# PL2303_HX.net
KiCad netlist of a schematic drawn in Altium Designer
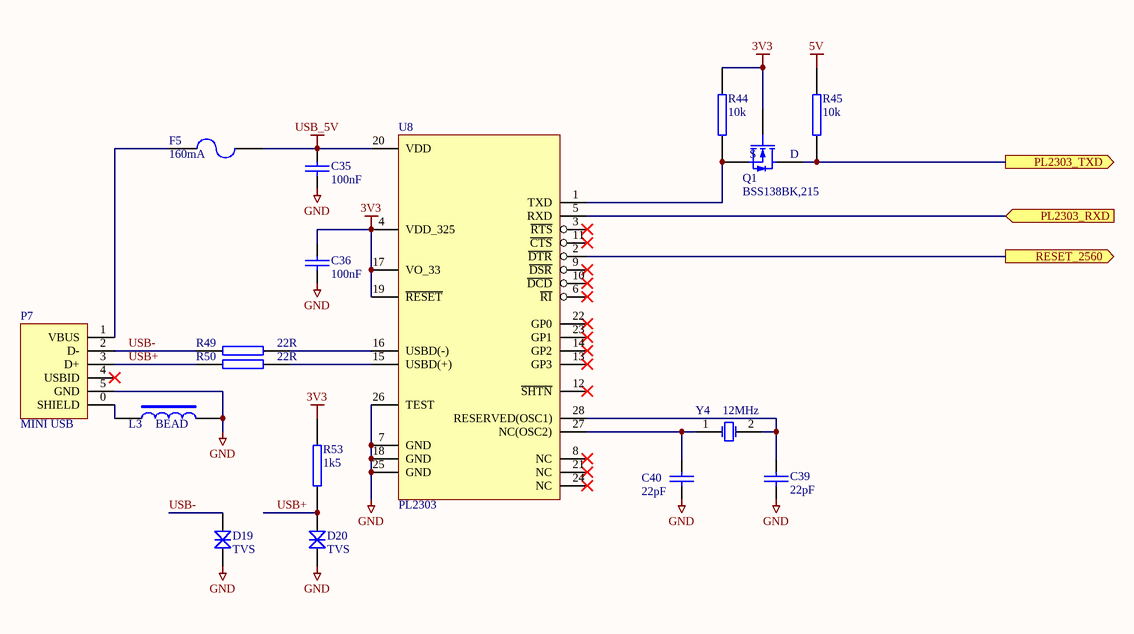
[diagram p0: PL2303(HX).SchDoc]

(export (version "E")
  (design (tool "Eeschema 10.0.6"))
  (components
    (comp (ref "C35")
      (value "100nF")
      (footprint "CAP (3D) - 0603")
      (description "CAPACITOR SMD 0603")
      (fields (field (name "MOUSER PART NO.") "81-GCM188R71C104KA7D") (field (name "MANUFACTURER") "Murata"))
      (libsource (lib "NASCO Capacitors") (part "CAP SMD 0603 100nF"))
    )
    (comp (ref "C36")
      (value "100nF")
      (footprint "CAP (3D) - 0603")
      (description "CAPACITOR SMD 0603")
      (fields (field (name "MOUSER PART NO.") "81-GCM188R71C104KA7D") (field (name "MANUFACTURER") "Murata"))
      (libsource (lib "NASCO Capacitors") (part "CAP SMD 0603 100nF"))
    )
    (comp (ref "C39")
      (value "22pF")
      (footprint "CAP (3D) - 0603")
      (description "CAPACITOR SMD 0603")
      (fields
        (field (name "MANUFACTURER") "Vishay")
        (field (name "MANUFACTURER PART NO.") "VJ0603A220JXACW1BC")
      )
      (libsource (lib "NASCO Capacitors") (part "CAP SMD 0603 1nF"))
    )
    (comp (ref "C40")
      (value "22pF")
      (footprint "CAP (3D) - 0603")
      (description "CAPACITOR SMD 0603")
      (fields
        (field (name "MANUFACTURER") "Vishay")
        (field (name "MANUFACTURER PART NO.") "VJ0603A220JXACW1BC")
      )
      (libsource (lib "NASCO Capacitors") (part "CAP SMD 0603 1nF"))
    )
    (comp (ref "D19")
      (value "TVS")
      (footprint "TVS (3D) - 0603")
      (description "Transient Voltage Suppression (TVS) Diode")
      (fields (field (name "MANUFACTURER PART NO.") "CG0603MLC-05E") (field (name "MANUFACTURER") "Bourns"))
      (libsource (lib "SIM900") (part "TVS DIODE"))
    )
    (comp (ref "D20")
      (value "TVS")
      (footprint "TVS (3D) - 0603")
      (description "Transient Voltage Suppression (TVS) Diode")
      (fields (field (name "MANUFACTURER PART NO.") "CG0603MLC-05E") (field (name "MANUFACTURER") "Bourns"))
      (libsource (lib "SIM900") (part "TVS DIODE"))
    )
    (comp (ref "F5")
      (value "160mA")
      (footprint "1206")
      (description "Fuse")
      (fields (field (name "MANUFACTURER") "Littlefuse") (field (name "MOUSER PART NO.") "576-1206L016WR"))
      (libsource (lib "Miscellaneous Devices") (part "Fuse 2"))
    )
    (comp (ref "L3")
      (value "BEAD")
      (footprint "RES (3D) - 1210")
      (description "INDUCTOR SMD 1210")
      (fields (field (name "MOUSER PART NO.") "636-2512063007Y3") (field (name "MANUFACTURER") "Fair-Rite"))
      (libsource (lib "NASCO") (part "INDUCTOR SMD 1210 100uH"))
    )
    (comp (ref "P7")
      (value "MINI USB")
      (footprint "MINI USB")
      (description "MICRO USB")
      (fields
        (field (name "MANUFACTURER") "Keystone Electronics")
        (field (name "MANUFACTURER PART NO.") "534-934")
      )
      (libsource (lib "SIM900") (part "MICRO USB"))
    )
    (comp (ref "Q1")
      (value "BSS138BK,215")
      (footprint "SOT23-3L")
      (description "N-Channel MOSFET")
      (fields
        (field (name "MANUFACTURER") "NXP Semiconductors")
        (field (name "MOUSER PART NO.") "771-BSS138BK215")
      )
      (libsource (lib "SIM900") (part "BSS138BK,215 SOT23"))
    )
    (comp (ref "R44")
      (value "10k")
      (footprint "RES (3D) - 0603")
      (description "RESISTOR SMD 0603 10k")
      (fields (field (name "MOUSER PART NO.") "652-CR0603FX-1002ELF") (field (name "MANUFACTURER") "Bourns"))
      (libsource (lib "NASCO Resistors") (part "RES SMD 0603 10k"))
    )
    (comp (ref "R45")
      (value "10k")
      (footprint "RES (3D) - 0603")
      (description "RESISTOR SMD 0603 10k")
      (fields (field (name "MOUSER PART NO.") "652-CR0603FX-1002ELF") (field (name "MANUFACTURER") "Bourns"))
      (libsource (lib "NASCO Resistors") (part "RES SMD 0603 10k"))
    )
    (comp (ref "R49")
      (value "22R")
      (footprint "RES (3D) - 0603")
      (description "RESISTOR SMD 0603 0R")
      (fields (field (name "MANUFACTURER") "Xicon") (field (name "MANUFACTURER PART NO.") "301-22-RC"))
      (libsource (lib "NASCO Resistors") (part "RES SMD 0603 0R"))
    )
    (comp (ref "R50")
      (value "22R")
      (footprint "RES (3D) - 0603")
      (description "RESISTOR SMD 0603 0R")
      (fields (field (name "MANUFACTURER") "Xicon") (field (name "MANUFACTURER PART NO.") "301-22-RC"))
      (libsource (lib "NASCO Resistors") (part "RES SMD 0603 0R"))
    )
    (comp (ref "R53")
      (value "1k5")
      (footprint "RES (3D) - 0603")
      (description "RESISTOR SMD 0603 0R")
      (libsource (lib "NASCO Resistors") (part "RES SMD 0603 0R"))
    )
    (comp (ref "U8")
      (value "PL2303")
      (footprint "SSOP28")
      (description "PL2303 USB to 232 Converter (FT232 Compatible)")
      (fields (field (name "MANUFACTURER") "PROLIFIC") (field (name "MANUFACTURER PART NO.") "PL2303TA"))
      (libsource (lib "NASCO") (part "PL2303"))
    )
    (comp (ref "Y4")
      (value "12MHz")
      (footprint "HC49/4H_SMX")
      (description "Crystal Oscillator")
      (fields (field (name "MANUFACTURER") "ECS"))
      (libsource (lib "Miscellaneous Devices") (part "XTAL"))
    )
  )
  (nets
    (net (code "1") (name "/PL2303_RXD") (class "Default")
      (node (ref "U8") (pin "5") (pinfunction "RXD_5") (pintype "passive"))
    )
    (net (code "2") (name "/PL2303_TXD") (class "Default")
      (node (ref "Q1") (pin "3") (pinfunction "D_3") (pintype "passive"))
      (node (ref "R45") (pin "1") (pinfunction "1_1") (pintype "passive"))
    )
    (net (code "3") (name "/RESET_2560") (class "Default")
      (node (ref "U8") (pin "2") (pinfunction "~{DTR}_2") (pintype "passive"))
    )
    (net (code "4") (name "/USB+") (class "Default")
      (node (ref "D20") (pin "2") (pinfunction "K_2") (pintype "passive"))
      (node (ref "P7") (pin "3") (pinfunction "D+_3") (pintype "passive"))
      (node (ref "R50") (pin "1") (pinfunction "1_1") (pintype "passive"))
      (node (ref "R53") (pin "2") (pinfunction "2_2") (pintype "passive"))
    )
    (net (code "5") (name "/USB-") (class "Default")
      (node (ref "D19") (pin "2") (pinfunction "K_2") (pintype "passive"))
      (node (ref "P7") (pin "2") (pinfunction "D-_2") (pintype "passive"))
      (node (ref "R49") (pin "1") (pinfunction "1_1") (pintype "passive"))
    )
    (net (code "6") (name "3V3") (class "Default")
      (node (ref "C36") (pin "1") (pinfunction "1_1") (pintype "passive"))
      (node (ref "Q1") (pin "1") (pinfunction "G_1") (pintype "passive"))
      (node (ref "R44") (pin "2") (pinfunction "2_2") (pintype "passive"))
      (node (ref "R53") (pin "1") (pinfunction "1_1") (pintype "passive"))
      (node (ref "U8") (pin "17") (pinfunction "VO_33_17") (pintype "passive"))
      (node (ref "U8") (pin "19") (pinfunction "~{RESET}_19") (pintype "passive"))
      (node (ref "U8") (pin "4") (pinfunction "VDD_325_4") (pintype "passive"))
    )
    (net (code "7") (name "5V") (class "Default")
      (node (ref "R45") (pin "2") (pinfunction "2_2") (pintype "passive"))
    )
    (net (code "8") (name "GND") (class "Default")
      (node (ref "C35") (pin "2") (pinfunction "2_2") (pintype "passive"))
      (node (ref "C36") (pin "2") (pinfunction "2_2") (pintype "passive"))
      (node (ref "C39") (pin "2") (pinfunction "2_2") (pintype "passive"))
      (node (ref "C40") (pin "2") (pinfunction "2_2") (pintype "passive"))
      (node (ref "D19") (pin "1") (pinfunction "A_1") (pintype "passive"))
      (node (ref "D20") (pin "1") (pinfunction "A_1") (pintype "passive"))
      (node (ref "L3") (pin "2") (pinfunction "2_2") (pintype "passive"))
      (node (ref "P7") (pin "5") (pinfunction "GND_5") (pintype "passive"))
      (node (ref "U8") (pin "18") (pinfunction "GND_18") (pintype "passive"))
      (node (ref "U8") (pin "25") (pinfunction "GND_25") (pintype "passive"))
      (node (ref "U8") (pin "26") (pinfunction "TEST_26") (pintype "passive"))
      (node (ref "U8") (pin "7") (pinfunction "GND_7") (pintype "passive"))
    )
    (net (code "9") (name "Net-(P7-SHIELD)") (class "Default")
      (node (ref "L3") (pin "1") (pinfunction "1_1") (pintype "passive"))
      (node (ref "P7") (pin "0") (pinfunction "SHIELD_0") (pintype "passive"))
    )
    (net (code "10") (name "Net-(P7-VBUS)") (class "Default")
      (node (ref "F5") (pin "1") (pinfunction "1_1") (pintype "passive"))
      (node (ref "P7") (pin "1") (pinfunction "VBUS_1") (pintype "passive"))
    )
    (net (code "11") (name "Net-(Q1-S)") (class "Default")
      (node (ref "Q1") (pin "2") (pinfunction "S_2") (pintype "passive"))
      (node (ref "R44") (pin "1") (pinfunction "1_1") (pintype "passive"))
      (node (ref "U8") (pin "1") (pinfunction "TXD_1") (pintype "passive"))
    )
    (net (code "12") (name "Net-(U8-NC(OSC2))") (class "Default")
      (node (ref "C40") (pin "1") (pinfunction "1_1") (pintype "passive"))
      (node (ref "U8") (pin "27") (pinfunction "NC(OSC2)_27") (pintype "passive"))
      (node (ref "Y4") (pin "1") (pinfunction "OSC1_1") (pintype "passive"))
    )
    (net (code "13") (name "Net-(U8-RESERVED(OSC1))") (class "Default")
      (node (ref "C39") (pin "1") (pinfunction "1_1") (pintype "passive"))
      (node (ref "U8") (pin "28") (pinfunction "RESERVED(OSC1)_28") (pintype "passive"))
      (node (ref "Y4") (pin "2") (pinfunction "OSC2_2") (pintype "passive"))
    )
    (net (code "14") (name "Net-(U8-USBD(+))") (class "Default")
      (node (ref "R50") (pin "2") (pinfunction "2_2") (pintype "passive"))
      (node (ref "U8") (pin "15") (pinfunction "USBD(+)_15") (pintype "passive"))
    )
    (net (code "15") (name "Net-(U8-USBD(-))") (class "Default")
      (node (ref "R49") (pin "2") (pinfunction "2_2") (pintype "passive"))
      (node (ref "U8") (pin "16") (pinfunction "USBD(-)_16") (pintype "passive"))
    )
    (net (code "16") (name "USB_5V") (class "Default")
      (node (ref "C35") (pin "1") (pinfunction "1_1") (pintype "passive"))
      (node (ref "F5") (pin "2") (pinfunction "2_2") (pintype "passive"))
      (node (ref "U8") (pin "20") (pinfunction "VDD_20") (pintype "passive"))
    )
    (net (code "17") (name "unconnected-(P7-USBID-Pad4)") (class "Default")
      (node (ref "P7") (pin "4") (pinfunction "USBID_4") (pintype "passive+no_connect"))
    )
    (net (code "18") (name "unconnected-(U8-GP0-Pad22)") (class "Default")
      (node (ref "U8") (pin "22") (pinfunction "GP0_22") (pintype "passive+no_connect"))
    )
    (net (code "19") (name "unconnected-(U8-GP1-Pad23)") (class "Default")
      (node (ref "U8") (pin "23") (pinfunction "GP1_23") (pintype "passive+no_connect"))
    )
    (net (code "20") (name "unconnected-(U8-GP2-Pad14)") (class "Default")
      (node (ref "U8") (pin "14") (pinfunction "GP2_14") (pintype "passive+no_connect"))
    )
    (net (code "21") (name "unconnected-(U8-GP3-Pad13)") (class "Default")
      (node (ref "U8") (pin "13") (pinfunction "GP3_13") (pintype "passive+no_connect"))
    )
    (net (code "22") (name "unconnected-(U8-NC-Pad8)") (class "Default")
      (node (ref "U8") (pin "8") (pinfunction "NC_8") (pintype "passive+no_connect"))
    )
    (net (code "23") (name "unconnected-(U8-NC-Pad21)") (class "Default")
      (node (ref "U8") (pin "21") (pinfunction "NC_21") (pintype "passive+no_connect"))
    )
    (net (code "24") (name "unconnected-(U8-NC-Pad24)") (class "Default")
      (node (ref "U8") (pin "24") (pinfunction "NC_24") (pintype "passive+no_connect"))
    )
    (net (code "25") (name "unconnected-(U8-~{CTS}-Pad11)") (class "Default")
      (node (ref "U8") (pin "11") (pinfunction "~{CTS}_11") (pintype "passive+no_connect"))
    )
    (net (code "26") (name "unconnected-(U8-~{DCD}-Pad10)") (class "Default")
      (node (ref "U8") (pin "10") (pinfunction "~{DCD}_10") (pintype "passive+no_connect"))
    )
    (net (code "27") (name "unconnected-(U8-~{DSR}-Pad9)") (class "Default")
      (node (ref "U8") (pin "9") (pinfunction "~{DSR}_9") (pintype "passive+no_connect"))
    )
    (net (code "28") (name "unconnected-(U8-~{RI}-Pad6)") (class "Default")
      (node (ref "U8") (pin "6") (pinfunction "~{RI}_6") (pintype "passive+no_connect"))
    )
    (net (code "29") (name "unconnected-(U8-~{RTS}-Pad3)") (class "Default")
      (node (ref "U8") (pin "3") (pinfunction "~{RTS}_3") (pintype "passive+no_connect"))
    )
    (net (code "30") (name "unconnected-(U8-~{SHTN}-Pad12)") (class "Default")
      (node (ref "U8") (pin "12") (pinfunction "~{SHTN}_12") (pintype "passive+no_connect"))
    )
  )
)
